# digit_6.net
KiCad netlist of a schematic drawn in EAGLE
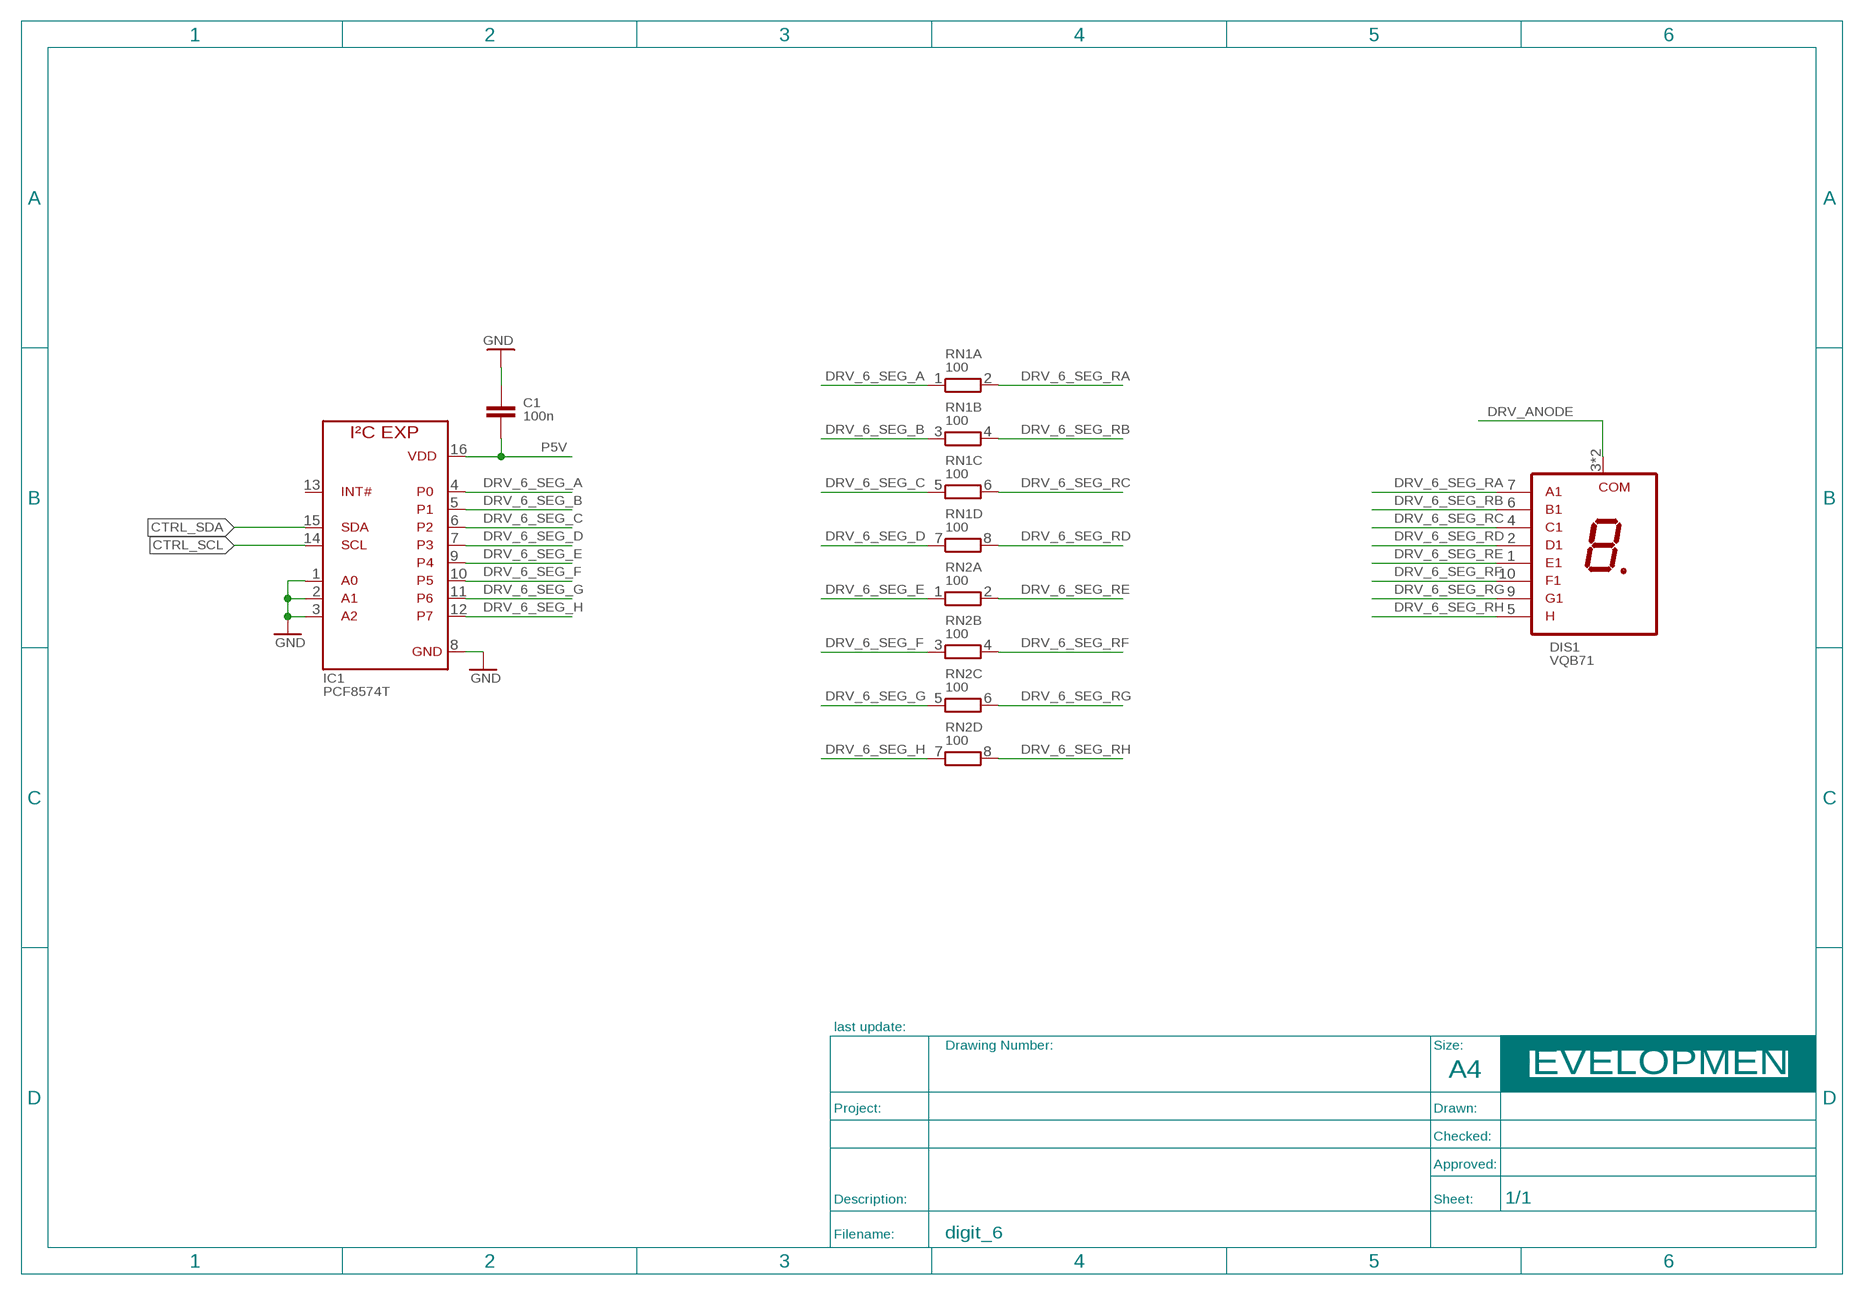
[diagram p0: schematic, sheet 1]

(export (version "E")
  (design (tool "Eeschema 10.0.6"))
  (components
    (comp (ref "C1")
      (value "100n")
      (footprint "eagle-import:S_0805")
      (fields (field (name "PART_CODE_BEL") "C_PAC_S_0805_VAL_100n"))
      (libsource (lib "eagle-import") (part "C_EU_S_0805"))
    )
    (comp (ref "DIS1")
      (value "VQB71")
      (footprint "eagle-import:T_VQB71")
      (libsource (lib "eagle-import") (part "VQB71"))
    )
    (comp (ref "IC1")
      (value "PCF8574T")
      (footprint "eagle-import:S_SOIC16")
      (libsource (lib "eagle-import") (part "PCF8574T"))
    )
    (comp (ref "RN1")
      (value "100")
      (footprint "eagle-import:T_SIL8")
      (fields (field (name "PART_CODE_BEL") "RN_PAC_T_SIL8_VAL_100"))
      (libsource (lib "eagle-import") (part "R_EU_ARRAY_4"))
    )
    (comp (ref "RN2")
      (value "100")
      (footprint "eagle-import:T_SIL8")
      (fields (field (name "PART_CODE_BEL") "RN_PAC_T_SIL8_VAL_100"))
      (libsource (lib "eagle-import") (part "R_EU_ARRAY_4"))
    )
  )
  (nets
    (net (code "1") (name "/DRV_6_SEG_A") (class "Default")
      (node (ref "IC1") (pin "4") (pinfunction "P0_4") (pintype "bidirectional"))
      (node (ref "RN1") (pin "1") (pinfunction "1_1") (pintype "passive"))
    )
    (net (code "2") (name "/DRV_6_SEG_B") (class "Default")
      (node (ref "IC1") (pin "5") (pinfunction "P1_5") (pintype "bidirectional"))
      (node (ref "RN1") (pin "3") (pinfunction "1_3") (pintype "passive"))
    )
    (net (code "3") (name "/DRV_6_SEG_C") (class "Default")
      (node (ref "IC1") (pin "6") (pinfunction "P2_6") (pintype "bidirectional"))
      (node (ref "RN1") (pin "5") (pinfunction "1_5") (pintype "passive"))
    )
    (net (code "4") (name "/DRV_6_SEG_D") (class "Default")
      (node (ref "IC1") (pin "7") (pinfunction "P3_7") (pintype "bidirectional"))
      (node (ref "RN1") (pin "7") (pinfunction "1_7") (pintype "passive"))
    )
    (net (code "5") (name "/DRV_6_SEG_E") (class "Default")
      (node (ref "IC1") (pin "9") (pinfunction "P4_9") (pintype "bidirectional"))
      (node (ref "RN2") (pin "1") (pinfunction "1_1") (pintype "passive"))
    )
    (net (code "6") (name "/DRV_6_SEG_F") (class "Default")
      (node (ref "IC1") (pin "10") (pinfunction "P5_10") (pintype "bidirectional"))
      (node (ref "RN2") (pin "3") (pinfunction "1_3") (pintype "passive"))
    )
    (net (code "7") (name "/DRV_6_SEG_G") (class "Default")
      (node (ref "IC1") (pin "11") (pinfunction "P6_11") (pintype "bidirectional"))
      (node (ref "RN2") (pin "5") (pinfunction "1_5") (pintype "passive"))
    )
    (net (code "8") (name "/DRV_6_SEG_H") (class "Default")
      (node (ref "IC1") (pin "12") (pinfunction "P7_12") (pintype "bidirectional"))
      (node (ref "RN2") (pin "7") (pinfunction "1_7") (pintype "passive"))
    )
    (net (code "9") (name "/DRV_6_SEG_RA") (class "Default")
      (node (ref "DIS1") (pin "7") (pinfunction "A1_7") (pintype "passive"))
      (node (ref "RN1") (pin "2") (pinfunction "2_2") (pintype "passive"))
    )
    (net (code "10") (name "/DRV_6_SEG_RB") (class "Default")
      (node (ref "DIS1") (pin "6") (pinfunction "B1_6") (pintype "passive"))
      (node (ref "RN1") (pin "4") (pinfunction "2_4") (pintype "passive"))
    )
    (net (code "11") (name "/DRV_6_SEG_RC") (class "Default")
      (node (ref "DIS1") (pin "4") (pinfunction "C1_4") (pintype "passive"))
      (node (ref "RN1") (pin "6") (pinfunction "2_6") (pintype "passive"))
    )
    (net (code "12") (name "/DRV_6_SEG_RD") (class "Default")
      (node (ref "DIS1") (pin "2") (pinfunction "D1_2") (pintype "passive"))
      (node (ref "RN1") (pin "8") (pinfunction "2_8") (pintype "passive"))
    )
    (net (code "13") (name "/DRV_6_SEG_RE") (class "Default")
      (node (ref "DIS1") (pin "1") (pinfunction "E1_1") (pintype "passive"))
      (node (ref "RN2") (pin "2") (pinfunction "2_2") (pintype "passive"))
    )
    (net (code "14") (name "/DRV_6_SEG_RF") (class "Default")
      (node (ref "DIS1") (pin "10") (pinfunction "F1_10") (pintype "passive"))
      (node (ref "RN2") (pin "4") (pinfunction "2_4") (pintype "passive"))
    )
    (net (code "15") (name "/DRV_6_SEG_RG") (class "Default")
      (node (ref "DIS1") (pin "9") (pinfunction "G1_9") (pintype "passive"))
      (node (ref "RN2") (pin "6") (pinfunction "2_6") (pintype "passive"))
    )
    (net (code "16") (name "/DRV_6_SEG_RH") (class "Default")
      (node (ref "DIS1") (pin "5") (pinfunction "DP1_5") (pintype "passive"))
      (node (ref "RN2") (pin "8") (pinfunction "2_8") (pintype "passive"))
    )
    (net (code "17") (name "/DRV_ANODE") (class "Default")
      (node (ref "DIS1") (pin "3") (pinfunction "COM1_3") (pintype "passive"))
      (node (ref "DIS1") (pin "8") (pinfunction "COM1_8") (pintype "passive"))
    )
    (net (code "18") (name "/P5V") (class "Default")
      (node (ref "C1") (pin "2") (pinfunction "2_2") (pintype "passive"))
      (node (ref "IC1") (pin "16") (pinfunction "VDD_16") (pintype "power_in"))
    )
    (net (code "19") (name "CTRL_SCL") (class "Default")
      (node (ref "IC1") (pin "14") (pinfunction "SCL_14") (pintype "input"))
    )
    (net (code "20") (name "CTRL_SDA") (class "Default")
      (node (ref "IC1") (pin "15") (pinfunction "SDA_15") (pintype "bidirectional"))
    )
    (net (code "21") (name "GND") (class "Default")
      (node (ref "C1") (pin "1") (pinfunction "1_1") (pintype "passive"))
      (node (ref "IC1") (pin "1") (pinfunction "A0_1") (pintype "input"))
      (node (ref "IC1") (pin "2") (pinfunction "A1_2") (pintype "input"))
      (node (ref "IC1") (pin "3") (pinfunction "A2_3") (pintype "input"))
      (node (ref "IC1") (pin "8") (pinfunction "GND_8") (pintype "power_in"))
    )
    (net (code "22") (name "unconnected-(IC1-~{INT}-Pad13)") (class "Default")
      (node (ref "IC1") (pin "13") (pinfunction "~{INT}_13") (pintype "output"))
    )
  )
)
